# LED_Lampe_v01.net
KiCad netlist of a schematic drawn in EAGLE
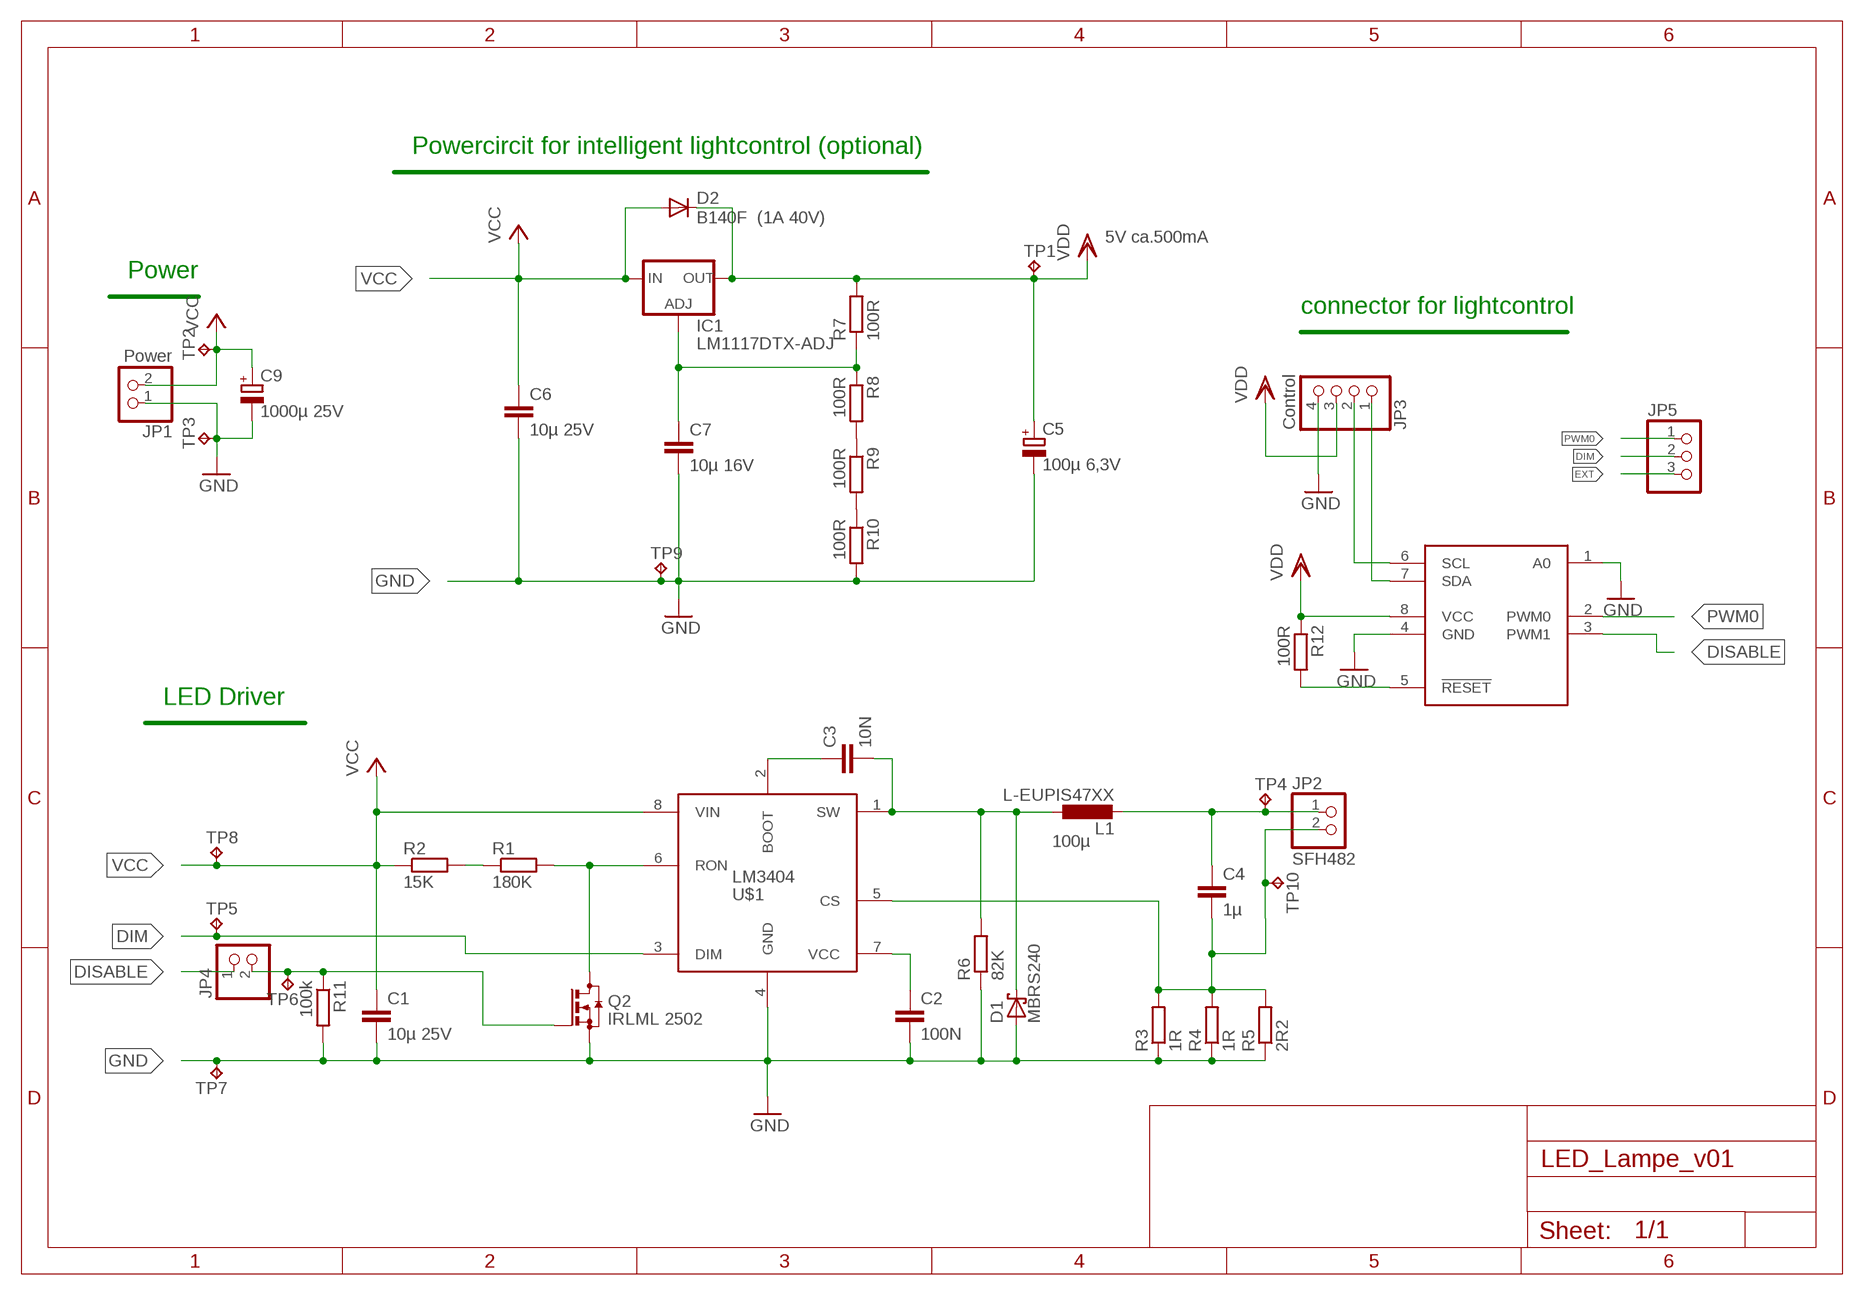
[diagram p0: schematic, sheet 1]

(export (version "E")
  (design (tool "Eeschema 10.0.6"))
  (components
    (comp (ref "C1")
      (value "10µ 25V")
      (footprint "eagle-import:C1206")
      (libsource (lib "eagle-import") (part "C-EUC1206"))
    )
    (comp (ref "C2")
      (value "100N")
      (footprint "eagle-import:C0805")
      (libsource (lib "eagle-import") (part "C-EUC0805"))
    )
    (comp (ref "C3")
      (value "10N")
      (footprint "eagle-import:C0805")
      (libsource (lib "eagle-import") (part "C-EUC0805"))
    )
    (comp (ref "C4")
      (value "1µ")
      (footprint "eagle-import:C0805")
      (libsource (lib "eagle-import") (part "C-EUC0805"))
    )
    (comp (ref "C5")
      (value "100µ 6,3V")
      (footprint "eagle-import:SMC_D")
      (libsource (lib "eagle-import") (part "CPOL-EUSMCD"))
    )
    (comp (ref "C6")
      (value "10µ 25V")
      (footprint "eagle-import:C1206")
      (libsource (lib "eagle-import") (part "C-EUC1206"))
    )
    (comp (ref "C7")
      (value "10µ 16V")
      (footprint "eagle-import:C1206")
      (libsource (lib "eagle-import") (part "C-EUC1206"))
    )
    (comp (ref "C9")
      (value "1000µ 25V")
      (footprint "eagle-import:153CLV-1014")
      (libsource (lib "eagle-import") (part "CPOL-EU153CLV-1014"))
    )
    (comp (ref "D1")
      (value "MBRS240")
      (footprint "eagle-import:SMB")
      (libsource (lib "eagle-import") (part "MBRS130LT3"))
    )
    (comp (ref "D2")
      (value "B140F (1A 40V)")
      (footprint "eagle-import:DO214AC")
      (libsource (lib "eagle-import") (part "DIODE-DO214AC"))
    )
    (comp (ref "IC1")
      (value "LM1117DTX-ADJ")
      (footprint "eagle-import:TO252")
      (libsource (lib "eagle-import") (part "LM1117DTX-ADJ"))
    )
    (comp (ref "JP1")
      (value "Power")
      (footprint "eagle-import:1X02SMD_90")
      (libsource (lib "eagle-import") (part "PINHD-1X2_2.54-SMD-90°"))
    )
    (comp (ref "JP2")
      (value "SFH482")
      (footprint "eagle-import:1X02SMD_90")
      (libsource (lib "eagle-import") (part "PINHD-1X2_2.54-SMD-90°"))
    )
    (comp (ref "JP3")
      (value "Control")
      (footprint "eagle-import:1X04SMD_90")
      (libsource (lib "eagle-import") (part "PINHD-1X4_2.54-SMD-90°"))
    )
    (comp (ref "JP4")
      (value "PINHD-1X2_2.54")
      (footprint "eagle-import:1X02")
      (libsource (lib "eagle-import") (part "pinhead-1_PINHD-1X2_2.54"))
    )
    (comp (ref "JP5")
      (value "PINHD-1X3_2.54")
      (footprint "eagle-import:1X03")
      (libsource (lib "eagle-import") (part "PINHD-1X3_2.54"))
    )
    (comp (ref "L1")
      (value "L-EUPIS47XX")
      (footprint "eagle-import:PIS47XX")
      (libsource (lib "eagle-import") (part "L-EUPIS47XX"))
    )
    (comp (ref "Q2")
      (value "IRLML 2502")
      (footprint "eagle-import:SOT23")
      (libsource (lib "eagle-import") (part "BSS123"))
    )
    (comp (ref "R1")
      (value "180K")
      (footprint "eagle-import:R0805")
      (libsource (lib "eagle-import") (part "R-EU_R0805"))
    )
    (comp (ref "R2")
      (value "15K")
      (footprint "eagle-import:R0805")
      (libsource (lib "eagle-import") (part "R-EU_R0805"))
    )
    (comp (ref "R3")
      (value "1R")
      (footprint "eagle-import:R0805")
      (libsource (lib "eagle-import") (part "R-EU_R0805"))
    )
    (comp (ref "R4")
      (value "1R")
      (footprint "eagle-import:R0805")
      (libsource (lib "eagle-import") (part "R-EU_R0805"))
    )
    (comp (ref "R5")
      (value "2R2")
      (footprint "eagle-import:R0805")
      (libsource (lib "eagle-import") (part "R-EU_R0805"))
    )
    (comp (ref "R6")
      (value "82K")
      (footprint "eagle-import:R0805")
      (libsource (lib "eagle-import") (part "R-EU_R0805"))
    )
    (comp (ref "R7")
      (value "100R")
      (footprint "eagle-import:R0805")
      (libsource (lib "eagle-import") (part "R-EU_R0805"))
    )
    (comp (ref "R8")
      (value "100R")
      (footprint "eagle-import:R0805")
      (libsource (lib "eagle-import") (part "R-EU_R0805"))
    )
    (comp (ref "R9")
      (value "100R")
      (footprint "eagle-import:R0805")
      (libsource (lib "eagle-import") (part "R-EU_R0805"))
    )
    (comp (ref "R10")
      (value "100R")
      (footprint "eagle-import:R0805")
      (libsource (lib "eagle-import") (part "R-EU_R0805"))
    )
    (comp (ref "R11")
      (value "100k")
      (footprint "eagle-import:R0805")
      (libsource (lib "eagle-import") (part "R-EU_R0805"))
    )
    (comp (ref "R12")
      (value "100R")
      (footprint "eagle-import:R0805")
      (libsource (lib "eagle-import") (part "R-EU_R0805"))
    )
    (comp (ref "TP1")
      (value "TP-040")
      (footprint "eagle-import:TP-040")
      (libsource (lib "eagle-import") (part "TP-040"))
    )
    (comp (ref "TP2")
      (value "TP-040")
      (footprint "eagle-import:TP-040")
      (libsource (lib "eagle-import") (part "TP-040"))
    )
    (comp (ref "TP3")
      (value "TP-040")
      (footprint "eagle-import:TP-040")
      (libsource (lib "eagle-import") (part "TP-040"))
    )
    (comp (ref "TP4")
      (value "TP-040")
      (footprint "eagle-import:TP-040")
      (libsource (lib "eagle-import") (part "TP-040"))
    )
    (comp (ref "TP5")
      (value "TP-040")
      (footprint "eagle-import:TP-040")
      (libsource (lib "eagle-import") (part "TP-040"))
    )
    (comp (ref "TP6")
      (value "TP-040")
      (footprint "eagle-import:TP-040")
      (libsource (lib "eagle-import") (part "TP-040"))
    )
    (comp (ref "TP7")
      (value "TP-040")
      (footprint "eagle-import:TP-040")
      (libsource (lib "eagle-import") (part "TP-040"))
    )
    (comp (ref "TP8")
      (value "TP-040")
      (footprint "eagle-import:TP-040")
      (libsource (lib "eagle-import") (part "TP-040"))
    )
    (comp (ref "TP9")
      (value "TP-040")
      (footprint "eagle-import:TP-040")
      (libsource (lib "eagle-import") (part "TP-040"))
    )
    (comp (ref "TP10")
      (value "TP-040")
      (footprint "eagle-import:TP-040")
      (libsource (lib "eagle-import") (part "TP-040"))
    )
    (comp (ref "U$1")
      (value "LM3404")
      (footprint "eagle-import:SO-8")
      (libsource (lib "eagle-import") (part "LM3404"))
    )
    (comp (ref "U$2")
      (value "PCA9530")
      (footprint "eagle-import:SO08")
      (libsource (lib "eagle-import") (part "PCA9530"))
    )
  )
  (nets
    (net (code "1") (name "DIM") (class "Default")
      (node (ref "JP5") (pin "2") (pinfunction "2_2") (pintype "passive"))
      (node (ref "TP5") (pin "1") (pinfunction "1_1") (pintype "passive"))
      (node (ref "U$1") (pin "3") (pinfunction "DIM_3") (pintype "input"))
    )
    (net (code "2") (name "DISABLE") (class "Default")
      (node (ref "JP4") (pin "1") (pinfunction "1_1") (pintype "passive"))
      (node (ref "U$2") (pin "3") (pinfunction "PWM1_3") (pintype "bidirectional"))
    )
    (net (code "3") (name "EXT") (class "Default")
      (node (ref "JP5") (pin "3") (pinfunction "3_3") (pintype "passive"))
    )
    (net (code "4") (name "GND") (class "Default")
      (node (ref "C1") (pin "2") (pinfunction "2_2") (pintype "passive"))
      (node (ref "C2") (pin "2") (pinfunction "2_2") (pintype "passive"))
      (node (ref "C5") (pin "-") (pinfunction "-_-") (pintype "passive"))
      (node (ref "C6") (pin "2") (pinfunction "2_2") (pintype "passive"))
      (node (ref "C7") (pin "2") (pinfunction "2_2") (pintype "passive"))
      (node (ref "C9") (pin "-") (pinfunction "-_-") (pintype "passive"))
      (node (ref "D1") (pin "A") (pinfunction "A_A") (pintype "passive"))
      (node (ref "JP1") (pin "1") (pinfunction "1_1") (pintype "passive"))
      (node (ref "JP3") (pin "4") (pinfunction "4_4") (pintype "passive"))
      (node (ref "Q2") (pin "2") (pinfunction "S_2") (pintype "passive"))
      (node (ref "R10") (pin "2") (pinfunction "2_2") (pintype "passive"))
      (node (ref "R11") (pin "2") (pinfunction "2_2") (pintype "passive"))
      (node (ref "R3") (pin "1") (pinfunction "1_1") (pintype "passive"))
      (node (ref "R4") (pin "1") (pinfunction "1_1") (pintype "passive"))
      (node (ref "R5") (pin "1") (pinfunction "1_1") (pintype "passive"))
      (node (ref "R6") (pin "1") (pinfunction "1_1") (pintype "passive"))
      (node (ref "TP3") (pin "1") (pinfunction "1_1") (pintype "passive"))
      (node (ref "TP7") (pin "1") (pinfunction "1_1") (pintype "passive"))
      (node (ref "TP9") (pin "1") (pinfunction "1_1") (pintype "passive"))
      (node (ref "U$1") (pin "4") (pinfunction "GND_4") (pintype "power_in"))
      (node (ref "U$2") (pin "1") (pinfunction "A0_1") (pintype "bidirectional"))
      (node (ref "U$2") (pin "4") (pinfunction "GND_4") (pintype "bidirectional"))
    )
    (net (code "5") (name "Net-(IC1-ADJ)") (class "Default")
      (node (ref "C7") (pin "1") (pinfunction "1_1") (pintype "passive"))
      (node (ref "IC1") (pin "1") (pinfunction "ADJ_1") (pintype "input"))
      (node (ref "R7") (pin "1") (pinfunction "1_1") (pintype "passive"))
      (node (ref "R8") (pin "1") (pinfunction "1_1") (pintype "passive"))
    )
    (net (code "6") (name "Net-(L1-1)") (class "Default")
      (node (ref "C3") (pin "2") (pinfunction "2_2") (pintype "passive"))
      (node (ref "D1") (pin "C") (pinfunction "C_C") (pintype "passive"))
      (node (ref "L1") (pin "2") (pinfunction "1_2") (pintype "passive"))
      (node (ref "R6") (pin "2") (pinfunction "2_2") (pintype "passive"))
      (node (ref "U$1") (pin "1") (pinfunction "SW_1") (pintype "bidirectional"))
    )
    (net (code "7") (name "Net-(L1-2)") (class "Default")
      (node (ref "C4") (pin "1") (pinfunction "1_1") (pintype "passive"))
      (node (ref "JP2") (pin "1") (pinfunction "1_1") (pintype "passive"))
      (node (ref "L1") (pin "1") (pinfunction "2_1") (pintype "passive"))
      (node (ref "TP4") (pin "1") (pinfunction "1_1") (pintype "passive"))
    )
    (net (code "8") (name "Net-(Q2-D)") (class "Default")
      (node (ref "Q2") (pin "3") (pinfunction "D_3") (pintype "passive"))
      (node (ref "R1") (pin "2") (pinfunction "2_2") (pintype "passive"))
      (node (ref "U$1") (pin "6") (pinfunction "RON_6") (pintype "bidirectional"))
    )
    (net (code "9") (name "Net-(Q2-G)") (class "Default")
      (node (ref "JP4") (pin "2") (pinfunction "2_2") (pintype "passive"))
      (node (ref "Q2") (pin "1") (pinfunction "G_1") (pintype "passive"))
      (node (ref "R11") (pin "1") (pinfunction "1_1") (pintype "passive"))
      (node (ref "TP6") (pin "1") (pinfunction "1_1") (pintype "passive"))
    )
    (net (code "10") (name "Net-(R1-Pad1)") (class "Default")
      (node (ref "R1") (pin "1") (pinfunction "1_1") (pintype "passive"))
      (node (ref "R2") (pin "2") (pinfunction "2_2") (pintype "passive"))
    )
    (net (code "11") (name "Net-(R8-Pad2)") (class "Default")
      (node (ref "R8") (pin "2") (pinfunction "2_2") (pintype "passive"))
      (node (ref "R9") (pin "1") (pinfunction "1_1") (pintype "passive"))
    )
    (net (code "12") (name "Net-(R10-Pad1)") (class "Default")
      (node (ref "R10") (pin "1") (pinfunction "1_1") (pintype "passive"))
      (node (ref "R9") (pin "2") (pinfunction "2_2") (pintype "passive"))
    )
    (net (code "13") (name "Net-(U$1-BOOT)") (class "Default")
      (node (ref "C3") (pin "1") (pinfunction "1_1") (pintype "passive"))
      (node (ref "U$1") (pin "2") (pinfunction "BOOT_2") (pintype "bidirectional"))
    )
    (net (code "14") (name "Net-(U$1-CS)") (class "Default")
      (node (ref "C4") (pin "2") (pinfunction "2_2") (pintype "passive"))
      (node (ref "JP2") (pin "2") (pinfunction "2_2") (pintype "passive"))
      (node (ref "R3") (pin "2") (pinfunction "2_2") (pintype "passive"))
      (node (ref "R4") (pin "2") (pinfunction "2_2") (pintype "passive"))
      (node (ref "R5") (pin "2") (pinfunction "2_2") (pintype "passive"))
      (node (ref "TP10") (pin "1") (pinfunction "1_1") (pintype "passive"))
      (node (ref "U$1") (pin "5") (pinfunction "CS_5") (pintype "bidirectional"))
    )
    (net (code "15") (name "Net-(U$1-VCC)") (class "Default")
      (node (ref "C2") (pin "1") (pinfunction "1_1") (pintype "passive"))
      (node (ref "U$1") (pin "7") (pinfunction "VCC_7") (pintype "output"))
    )
    (net (code "16") (name "Net-(U$2-SCL)") (class "Default")
      (node (ref "JP3") (pin "2") (pinfunction "2_2") (pintype "passive"))
      (node (ref "U$2") (pin "6") (pinfunction "SCL_6") (pintype "bidirectional"))
    )
    (net (code "17") (name "Net-(U$2-SDA)") (class "Default")
      (node (ref "JP3") (pin "1") (pinfunction "1_1") (pintype "passive"))
      (node (ref "U$2") (pin "7") (pinfunction "SDA_7") (pintype "bidirectional"))
    )
    (net (code "18") (name "Net-(U$2-~{RESET})") (class "Default")
      (node (ref "R12") (pin "2") (pinfunction "2_2") (pintype "passive"))
      (node (ref "U$2") (pin "5") (pinfunction "~{RESET}_5") (pintype "bidirectional"))
    )
    (net (code "19") (name "PWM0") (class "Default")
      (node (ref "JP5") (pin "1") (pinfunction "1_1") (pintype "passive"))
      (node (ref "U$2") (pin "2") (pinfunction "PWM0_2") (pintype "bidirectional"))
    )
    (net (code "20") (name "VCC") (class "Default")
      (node (ref "C1") (pin "1") (pinfunction "1_1") (pintype "passive"))
      (node (ref "C6") (pin "1") (pinfunction "1_1") (pintype "passive"))
      (node (ref "C9") (pin "+") (pinfunction "+_+") (pintype "passive"))
      (node (ref "D2") (pin "A") (pinfunction "A_A") (pintype "passive"))
      (node (ref "IC1") (pin "2") (pinfunction "IN_2") (pintype "input"))
      (node (ref "JP1") (pin "2") (pinfunction "2_2") (pintype "passive"))
      (node (ref "R2") (pin "1") (pinfunction "1_1") (pintype "passive"))
      (node (ref "TP2") (pin "1") (pinfunction "1_1") (pintype "passive"))
      (node (ref "TP8") (pin "1") (pinfunction "1_1") (pintype "passive"))
      (node (ref "U$1") (pin "8") (pinfunction "VIN_8") (pintype "power_in"))
    )
    (net (code "21") (name "VDD") (class "Default")
      (node (ref "C5") (pin "+") (pinfunction "+_+") (pintype "passive"))
      (node (ref "D2") (pin "C") (pinfunction "C_C") (pintype "passive"))
      (node (ref "IC1") (pin "TAB") (pinfunction "OUT_TAB") (pintype "passive"))
      (node (ref "JP3") (pin "3") (pinfunction "3_3") (pintype "passive"))
      (node (ref "R12") (pin "1") (pinfunction "1_1") (pintype "passive"))
      (node (ref "R7") (pin "2") (pinfunction "2_2") (pintype "passive"))
      (node (ref "TP1") (pin "1") (pinfunction "1_1") (pintype "passive"))
      (node (ref "U$2") (pin "8") (pinfunction "VCC_8") (pintype "bidirectional"))
    )
  )
)
